# Duckuino.net
KiCad netlist of a schematic drawn in EAGLE
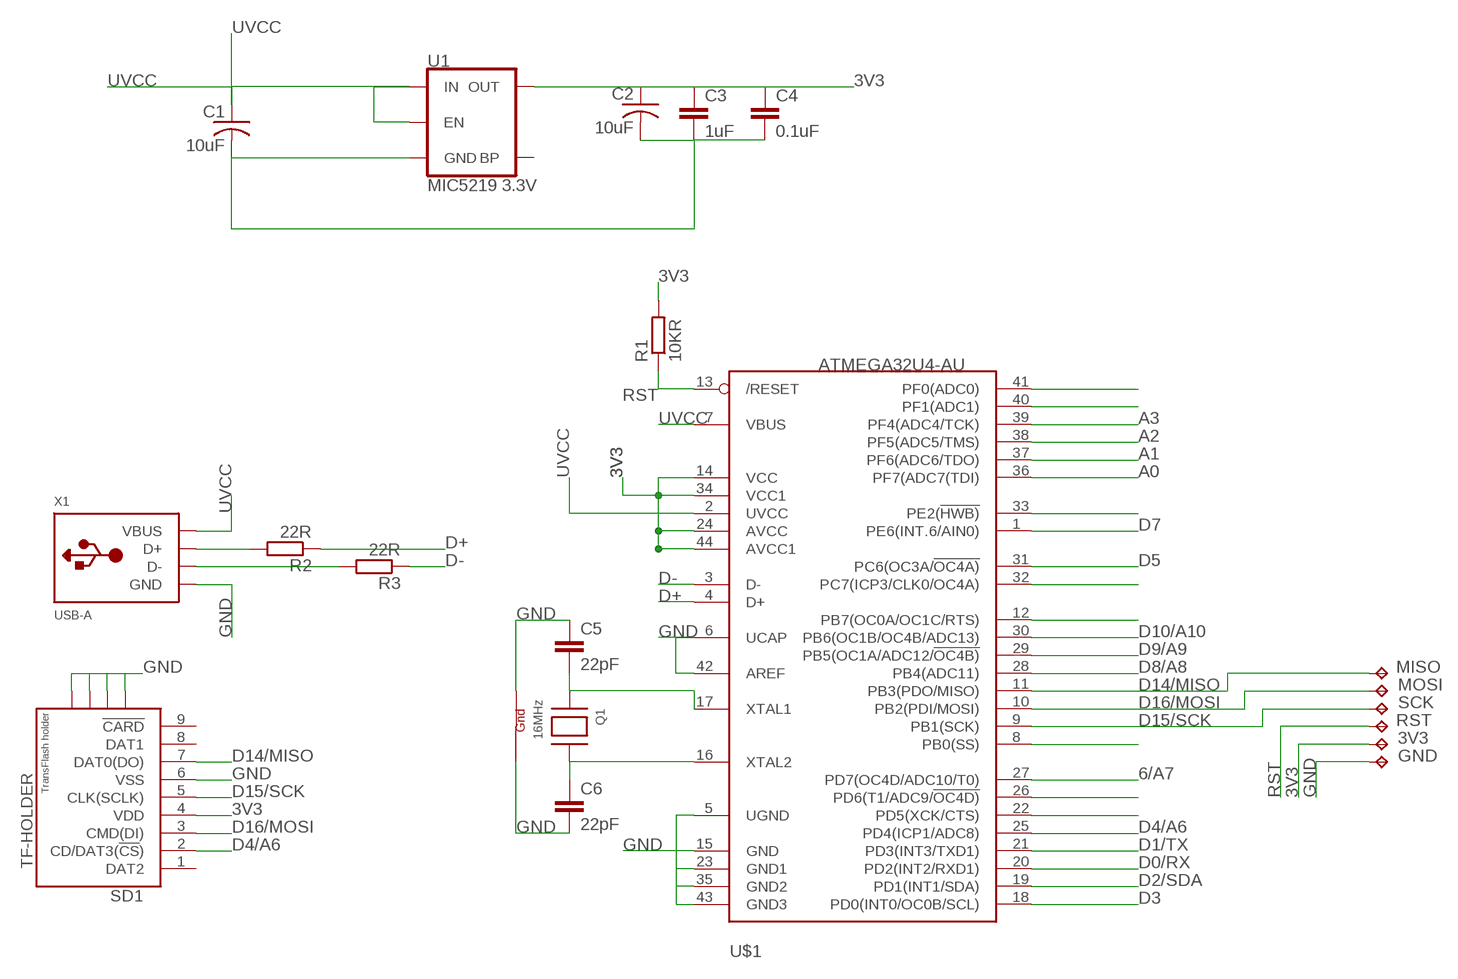
[diagram p0: schematic, sheet 1]

(export (version "E")
  (design (tool "Eeschema 10.0.6"))
  (components
    (comp (ref "3V3")
      (value "TPTP11R")
      (footprint "eagle-import:TP11R")
      (libsource (lib "eagle-import") (part "TPTP11R"))
    )
    (comp (ref "C1")
      (value "10uF")
      (footprint "eagle-import:C0603")
      (libsource (lib "eagle-import") (part "C-USC0603"))
    )
    (comp (ref "C2")
      (value "10uF")
      (footprint "eagle-import:C0603")
      (libsource (lib "eagle-import") (part "C-USC0603"))
    )
    (comp (ref "C3")
      (value "1uF")
      (footprint "eagle-import:C0603")
      (libsource (lib "eagle-import") (part "C-EUC0603"))
    )
    (comp (ref "C4")
      (value "0.1uF")
      (footprint "eagle-import:C0603")
      (libsource (lib "eagle-import") (part "C-EUC0603"))
    )
    (comp (ref "C5")
      (value "22pF")
      (footprint "eagle-import:C0603")
      (libsource (lib "eagle-import") (part "C-EUC0603"))
    )
    (comp (ref "C6")
      (value "22pF")
      (footprint "eagle-import:C0603")
      (libsource (lib "eagle-import") (part "C-EUC0603"))
    )
    (comp (ref "GND")
      (value "TPTP11R")
      (footprint "eagle-import:TP11R")
      (libsource (lib "eagle-import") (part "TPTP11R"))
    )
    (comp (ref "MISO")
      (value "TPTP11R")
      (footprint "eagle-import:TP11R")
      (libsource (lib "eagle-import") (part "TPTP11R"))
    )
    (comp (ref "MOSI")
      (value "TPTP11R")
      (footprint "eagle-import:TP11R")
      (libsource (lib "eagle-import") (part "TPTP11R"))
    )
    (comp (ref "Q1")
      (value "16MHz")
      (footprint "eagle-import:NX3225")
      (libsource (lib "eagle-import") (part "XTAL-4-3225"))
    )
    (comp (ref "R1")
      (value "10KR")
      (footprint "eagle-import:R0603")
      (libsource (lib "eagle-import") (part "RR0603"))
    )
    (comp (ref "R2")
      (value "22R")
      (footprint "eagle-import:R0603")
      (libsource (lib "eagle-import") (part "RR0603"))
    )
    (comp (ref "R3")
      (value "22R")
      (footprint "eagle-import:R0603")
      (libsource (lib "eagle-import") (part "RR0603"))
    )
    (comp (ref "RST")
      (value "TPTP11R")
      (footprint "eagle-import:TP11R")
      (libsource (lib "eagle-import") (part "TPTP11R"))
    )
    (comp (ref "SCK")
      (value "TPTP11R")
      (footprint "eagle-import:TP11R")
      (libsource (lib "eagle-import") (part "TPTP11R"))
    )
    (comp (ref "SD1")
      (value "TF-HOLDER")
      (footprint "eagle-import:TF-PULL")
      (libsource (lib "eagle-import") (part "TF-HOLDER"))
    )
    (comp (ref "U$1")
      (value "ATMEGA32U4-AU")
      (footprint "eagle-import:TQFP44")
      (libsource (lib "eagle-import") (part "ATMEGA32U4-AU"))
    )
    (comp (ref "U1")
      (value "MIC5219 3.3V")
      (footprint "eagle-import:SOT23-5")
      (libsource (lib "eagle-import") (part "V_REG_MIC52193.3V"))
    )
    (comp (ref "X1")
      (value "USB-A")
      (footprint "eagle-import:MOLEX_480371000")
      (libsource (lib "eagle-import") (part "USB-A"))
    )
  )
  (nets
    (net (code "1") (name "/3V3") (class "Default")
      (node (ref "3V3") (pin "TP") (pinfunction "TP_TP") (pintype "input"))
      (node (ref "C2") (pin "1") (pinfunction "1_1") (pintype "passive"))
      (node (ref "C3") (pin "1") (pinfunction "1_1") (pintype "passive"))
      (node (ref "C4") (pin "1") (pinfunction "1_1") (pintype "passive"))
      (node (ref "R1") (pin "2") (pinfunction "2_2") (pintype "passive"))
      (node (ref "SD1") (pin "4") (pinfunction "VDD_4") (pintype "power_in"))
      (node (ref "U$1") (pin "14") (pinfunction "VCC_14") (pintype "bidirectional"))
      (node (ref "U$1") (pin "24") (pinfunction "AVCC_24") (pintype "bidirectional"))
      (node (ref "U$1") (pin "34") (pinfunction "VCC1_34") (pintype "bidirectional"))
      (node (ref "U$1") (pin "44") (pinfunction "AVCC1_44") (pintype "bidirectional"))
      (node (ref "U1") (pin "5") (pinfunction "OUT_5") (pintype "passive"))
    )
    (net (code "2") (name "/6{slash}A7") (class "Default")
      (node (ref "U$1") (pin "27") (pinfunction "PD7(OC4D/ADC10/T0)_27") (pintype "bidirectional"))
    )
    (net (code "3") (name "/A0") (class "Default")
      (node (ref "U$1") (pin "36") (pinfunction "PF7(ADC7(TDI)_36") (pintype "bidirectional"))
    )
    (net (code "4") (name "/A1") (class "Default")
      (node (ref "U$1") (pin "37") (pinfunction "PF6(ADC6/TDO)_37") (pintype "bidirectional"))
    )
    (net (code "5") (name "/A2") (class "Default")
      (node (ref "U$1") (pin "38") (pinfunction "PF5(ADC5/TMS)_38") (pintype "bidirectional"))
    )
    (net (code "6") (name "/A3") (class "Default")
      (node (ref "U$1") (pin "39") (pinfunction "PF4(ADC4/TCK)_39") (pintype "bidirectional"))
    )
    (net (code "7") (name "/D+") (class "Default")
      (node (ref "R2") (pin "1") (pinfunction "1_1") (pintype "passive"))
      (node (ref "U$1") (pin "4") (pinfunction "D+_4") (pintype "bidirectional"))
    )
    (net (code "8") (name "/D-") (class "Default")
      (node (ref "R3") (pin "1") (pinfunction "1_1") (pintype "passive"))
      (node (ref "U$1") (pin "3") (pinfunction "D-_3") (pintype "bidirectional"))
    )
    (net (code "9") (name "/D0{slash}RX") (class "Default")
      (node (ref "U$1") (pin "20") (pinfunction "PD2(INT2/RXD1)_20") (pintype "bidirectional"))
    )
    (net (code "10") (name "/D1{slash}TX") (class "Default")
      (node (ref "U$1") (pin "21") (pinfunction "PD3(INT3/TXD1)_21") (pintype "bidirectional"))
    )
    (net (code "11") (name "/D2{slash}SDA") (class "Default")
      (node (ref "U$1") (pin "19") (pinfunction "PD1(INT1/SDA)_19") (pintype "bidirectional"))
    )
    (net (code "12") (name "/D3") (class "Default")
      (node (ref "U$1") (pin "18") (pinfunction "PD0(INT0/OC0B/SCL)_18") (pintype "bidirectional"))
    )
    (net (code "13") (name "/D4{slash}A6") (class "Default")
      (node (ref "SD1") (pin "2") (pinfunction "CD/DAT3(~{CS})_2") (pintype "bidirectional"))
      (node (ref "U$1") (pin "25") (pinfunction "PD4(ICP1/ADC8)_25") (pintype "bidirectional"))
    )
    (net (code "14") (name "/D5") (class "Default")
      (node (ref "U$1") (pin "31") (pinfunction "PC6(OC3A/~{OC4A})_31") (pintype "bidirectional"))
    )
    (net (code "15") (name "/D7") (class "Default")
      (node (ref "U$1") (pin "1") (pinfunction "PE6(INT.6/AIN0)_1") (pintype "bidirectional"))
    )
    (net (code "16") (name "/D8{slash}A8") (class "Default")
      (node (ref "U$1") (pin "28") (pinfunction "PB4(ADC11)_28") (pintype "bidirectional"))
    )
    (net (code "17") (name "/D9{slash}A9") (class "Default")
      (node (ref "U$1") (pin "29") (pinfunction "PB5(OC1A/ADC12/~{OC4B})_29") (pintype "bidirectional"))
    )
    (net (code "18") (name "/D10{slash}A10") (class "Default")
      (node (ref "U$1") (pin "30") (pinfunction "PB6(OC1B/OC4B/ADC13)_30") (pintype "bidirectional"))
    )
    (net (code "19") (name "/D14{slash}MISO") (class "Default")
      (node (ref "MISO") (pin "TP") (pinfunction "TP_TP") (pintype "input"))
      (node (ref "SD1") (pin "7") (pinfunction "DAT0(DO)_7") (pintype "bidirectional"))
      (node (ref "U$1") (pin "11") (pinfunction "PB3(PDO/MISO)_11") (pintype "bidirectional"))
    )
    (net (code "20") (name "/D15{slash}SCK") (class "Default")
      (node (ref "SCK") (pin "TP") (pinfunction "TP_TP") (pintype "input"))
      (node (ref "SD1") (pin "5") (pinfunction "CLK(SCLK)_5") (pintype "input"))
      (node (ref "U$1") (pin "9") (pinfunction "PB1(SCK)_9") (pintype "bidirectional"))
    )
    (net (code "21") (name "/D16{slash}MOSI") (class "Default")
      (node (ref "MOSI") (pin "TP") (pinfunction "TP_TP") (pintype "input"))
      (node (ref "SD1") (pin "3") (pinfunction "CMD(DI)_3") (pintype "bidirectional"))
      (node (ref "U$1") (pin "10") (pinfunction "PB2(PDI/MOSI)_10") (pintype "bidirectional"))
    )
    (net (code "22") (name "/GND") (class "Default")
      (node (ref "C1") (pin "2") (pinfunction "2_2") (pintype "passive"))
      (node (ref "C2") (pin "2") (pinfunction "2_2") (pintype "passive"))
      (node (ref "C3") (pin "2") (pinfunction "2_2") (pintype "passive"))
      (node (ref "C4") (pin "2") (pinfunction "2_2") (pintype "passive"))
      (node (ref "C5") (pin "1") (pinfunction "1_1") (pintype "passive"))
      (node (ref "C6") (pin "2") (pinfunction "2_2") (pintype "passive"))
      (node (ref "GND") (pin "TP") (pinfunction "TP_TP") (pintype "input"))
      (node (ref "Q1") (pin "2") (pinfunction "G2_2") (pintype "power_in"))
      (node (ref "Q1") (pin "4") (pinfunction "G1_4") (pintype "power_in"))
      (node (ref "SD1") (pin "6") (pinfunction "VSS_6") (pintype "power_in"))
      (node (ref "SD1") (pin "S1") (pinfunction "S1_S1") (pintype "passive"))
      (node (ref "SD1") (pin "S2") (pinfunction "S2_S2") (pintype "passive"))
      (node (ref "SD1") (pin "S3") (pinfunction "S3_S3") (pintype "passive"))
      (node (ref "SD1") (pin "S4") (pinfunction "S4_S4") (pintype "passive"))
      (node (ref "U$1") (pin "15") (pinfunction "GND_15") (pintype "bidirectional"))
      (node (ref "U$1") (pin "23") (pinfunction "GND1_23") (pintype "bidirectional"))
      (node (ref "U$1") (pin "35") (pinfunction "GND2_35") (pintype "bidirectional"))
      (node (ref "U$1") (pin "42") (pinfunction "AREF_42") (pintype "bidirectional"))
      (node (ref "U$1") (pin "43") (pinfunction "GND3_43") (pintype "bidirectional"))
      (node (ref "U$1") (pin "5") (pinfunction "UGND_5") (pintype "bidirectional"))
      (node (ref "U$1") (pin "6") (pinfunction "UCAP_6") (pintype "bidirectional"))
      (node (ref "U1") (pin "2") (pinfunction "GND_2") (pintype "input"))
      (node (ref "X1") (pin "4") (pinfunction "GND_4") (pintype "power_in"))
    )
    (net (code "23") (name "/RST") (class "Default")
      (node (ref "R1") (pin "1") (pinfunction "1_1") (pintype "passive"))
      (node (ref "RST") (pin "TP") (pinfunction "TP_TP") (pintype "input"))
      (node (ref "U$1") (pin "13") (pinfunction "/RESET_13") (pintype "bidirectional"))
    )
    (net (code "24") (name "/UVCC") (class "Default")
      (node (ref "C1") (pin "1") (pinfunction "1_1") (pintype "passive"))
      (node (ref "U$1") (pin "2") (pinfunction "UVCC_2") (pintype "bidirectional"))
      (node (ref "U$1") (pin "7") (pinfunction "VBUS_7") (pintype "bidirectional"))
      (node (ref "U1") (pin "1") (pinfunction "IN_1") (pintype "input"))
      (node (ref "U1") (pin "3") (pinfunction "EN_3") (pintype "input"))
      (node (ref "X1") (pin "1") (pinfunction "VBUS_1") (pintype "power_in"))
    )
    (net (code "25") (name "Net-(Q1-X1)") (class "Default")
      (node (ref "C5") (pin "2") (pinfunction "2_2") (pintype "passive"))
      (node (ref "Q1") (pin "1") (pinfunction "X1_1") (pintype "bidirectional"))
      (node (ref "U$1") (pin "17") (pinfunction "XTAL1_17") (pintype "bidirectional"))
    )
    (net (code "26") (name "Net-(Q1-X2)") (class "Default")
      (node (ref "C6") (pin "1") (pinfunction "1_1") (pintype "passive"))
      (node (ref "Q1") (pin "3") (pinfunction "X2_3") (pintype "bidirectional"))
      (node (ref "U$1") (pin "16") (pinfunction "XTAL2_16") (pintype "bidirectional"))
    )
    (net (code "27") (name "Net-(X1-D+)") (class "Default")
      (node (ref "R2") (pin "2") (pinfunction "2_2") (pintype "passive"))
      (node (ref "X1") (pin "3") (pinfunction "D+_3") (pintype "bidirectional"))
    )
    (net (code "28") (name "Net-(X1-D-)") (class "Default")
      (node (ref "R3") (pin "2") (pinfunction "2_2") (pintype "passive"))
      (node (ref "X1") (pin "2") (pinfunction "D-_2") (pintype "bidirectional"))
    )
    (net (code "29") (name "unconnected-(SD1-DAT1-Pad8)") (class "Default")
      (node (ref "SD1") (pin "8") (pinfunction "DAT1_8") (pintype "bidirectional"))
    )
    (net (code "30") (name "unconnected-(SD1-DAT2-Pad1)") (class "Default")
      (node (ref "SD1") (pin "1") (pinfunction "DAT2_1") (pintype "bidirectional"))
    )
    (net (code "31") (name "unconnected-(SD1-~{CARD}-Pad9)") (class "Default")
      (node (ref "SD1") (pin "9") (pinfunction "~{CARD}_9") (pintype "passive"))
    )
    (net (code "32") (name "unconnected-(U$1-PB0(SS)-Pad8)") (class "Default")
      (node (ref "U$1") (pin "8") (pinfunction "PB0(SS)_8") (pintype "bidirectional"))
    )
    (net (code "33") (name "unconnected-(U$1-PB7(OC0A{slash}OC1C{slash}RTS)-Pad12)") (class "Default")
      (node (ref "U$1") (pin "12") (pinfunction "PB7(OC0A/OC1C/RTS)_12") (pintype "bidirectional"))
    )
    (net (code "34") (name "unconnected-(U$1-PC7(ICP3{slash}CLK0{slash}OC4A)-Pad32)") (class "Default")
      (node (ref "U$1") (pin "32") (pinfunction "PC7(ICP3/CLK0/OC4A)_32") (pintype "bidirectional"))
    )
    (net (code "35") (name "unconnected-(U$1-PD5(XCK{slash}CTS)-Pad22)") (class "Default")
      (node (ref "U$1") (pin "22") (pinfunction "PD5(XCK/CTS)_22") (pintype "bidirectional"))
    )
    (net (code "36") (name "unconnected-(U$1-PD6(T1{slash}ADC9{slash}~{OC4D})-Pad26)") (class "Default")
      (node (ref "U$1") (pin "26") (pinfunction "PD6(T1/ADC9/~{OC4D})_26") (pintype "bidirectional"))
    )
    (net (code "37") (name "unconnected-(U$1-PE2(~{HWB})-Pad33)") (class "Default")
      (node (ref "U$1") (pin "33") (pinfunction "PE2(~{HWB})_33") (pintype "bidirectional"))
    )
    (net (code "38") (name "unconnected-(U$1-PF0(ADC0)-Pad41)") (class "Default")
      (node (ref "U$1") (pin "41") (pinfunction "PF0(ADC0)_41") (pintype "bidirectional"))
    )
    (net (code "39") (name "unconnected-(U$1-PF1(ADC1)-Pad40)") (class "Default")
      (node (ref "U$1") (pin "40") (pinfunction "PF1(ADC1)_40") (pintype "bidirectional"))
    )
    (net (code "40") (name "unconnected-(U1-BP-Pad4)") (class "Default")
      (node (ref "U1") (pin "4") (pinfunction "BP_4") (pintype "input"))
    )
  )
)
